# IP_04_00_000-PendulumSchem.net
KiCad netlist of a schematic drawn in EAGLE
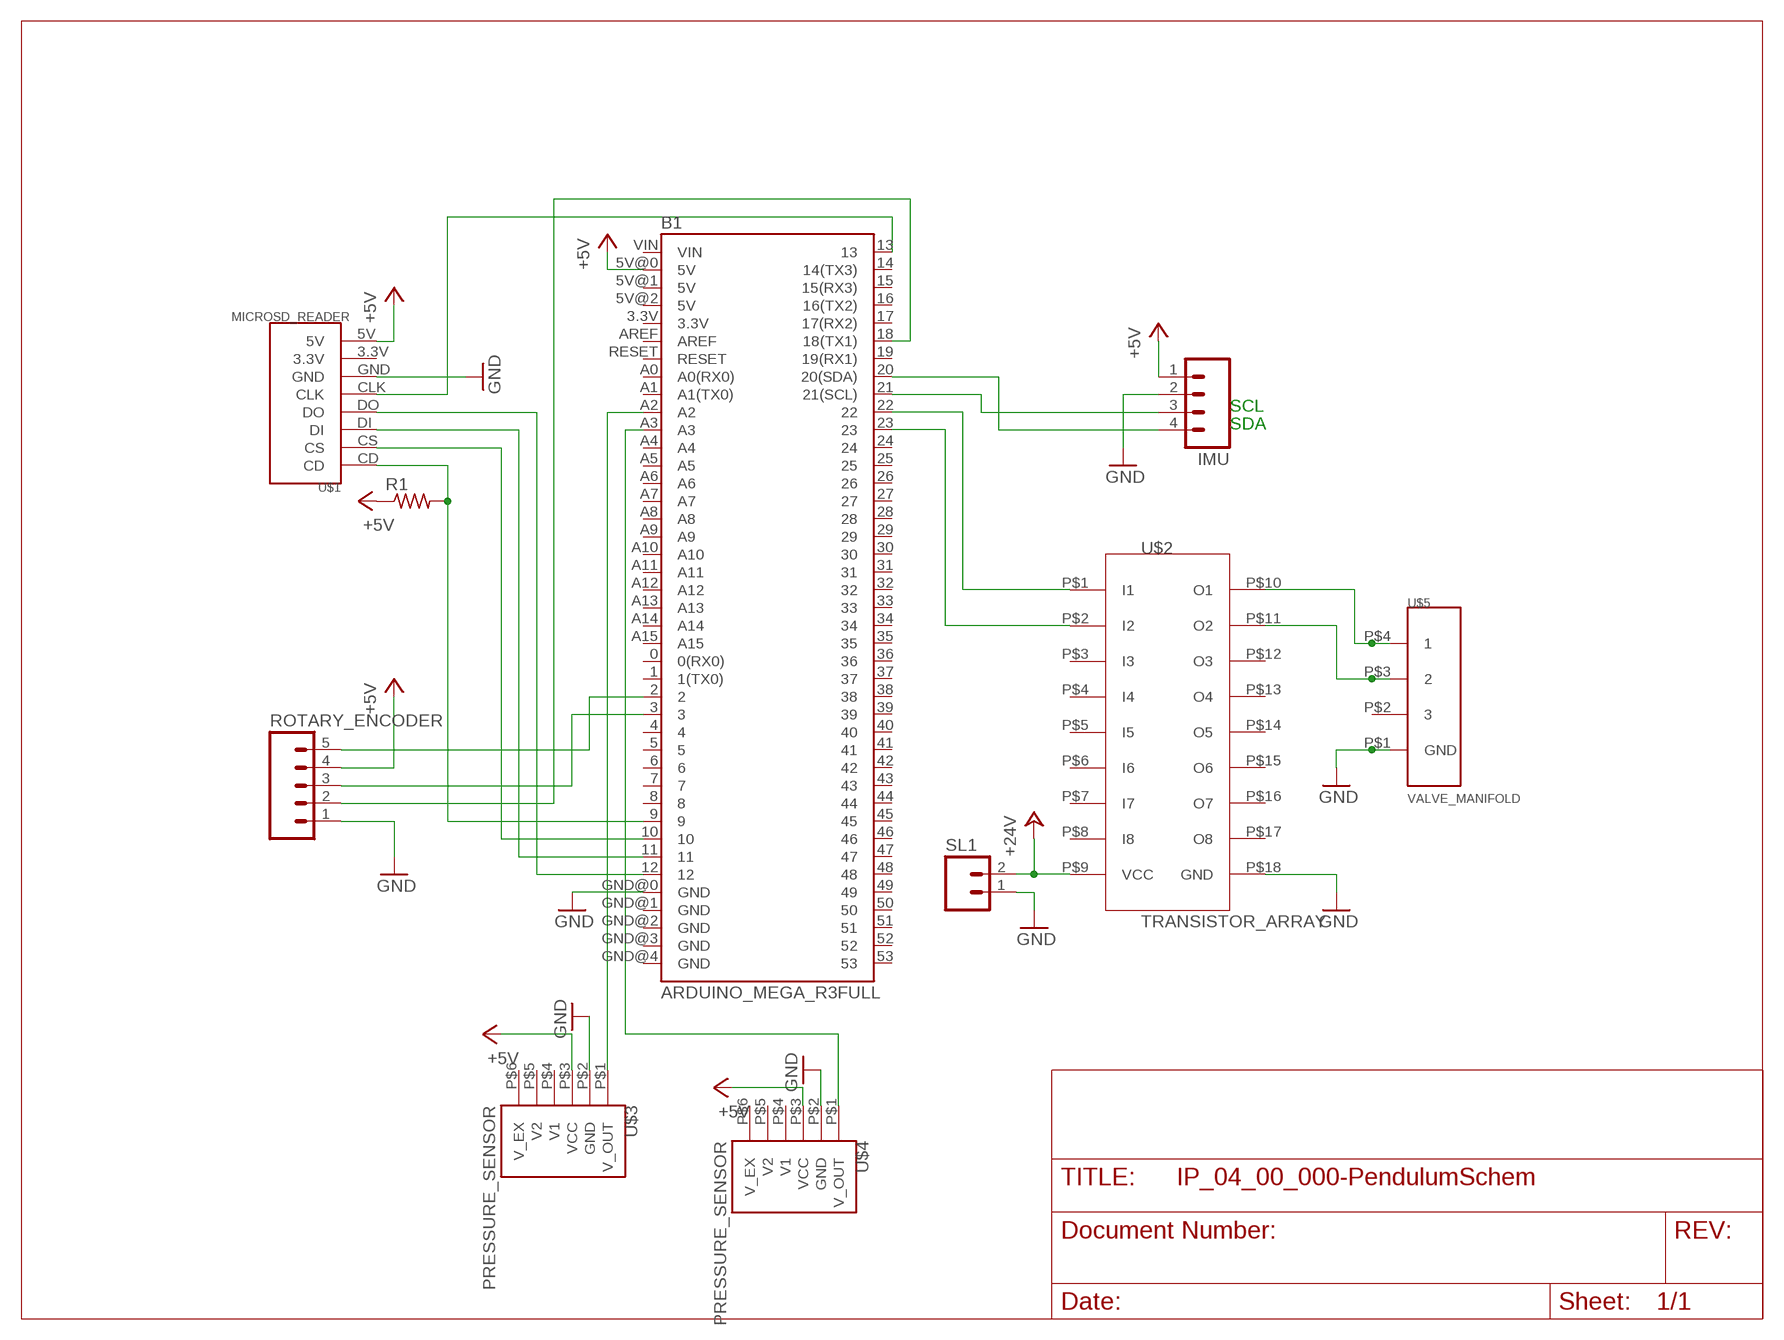
[diagram p0: schematic, sheet 1]

(export (version "E")
  (design (tool "Eeschema 10.0.6"))
  (components
    (comp (ref "B1")
      (value "ARDUINO_MEGA_R3FULL")
      (footprint "eagle-import:ARDUINO_MEGA")
      (libsource (lib "eagle-import") (part "ARDUINO_MEGA_R3FULL"))
    )
    (comp (ref "IMU")
      (value "M04")
      (footprint "eagle-import:04P")
      (libsource (lib "eagle-import") (part "M04"))
    )
    (comp (ref "R1")
      (value "R-US_0204/7")
      (footprint "eagle-import:0204_7")
      (libsource (lib "eagle-import") (part "R-US_0204/7"))
    )
    (comp (ref "ROTARY_ENCODER")
      (value "M05")
      (footprint "eagle-import:05P")
      (libsource (lib "eagle-import") (part "M05"))
    )
    (comp (ref "SL1")
      (value "M02")
      (footprint "eagle-import:02P")
      (libsource (lib "eagle-import") (part "M02"))
    )
    (comp (ref "U$1")
      (value "MICROSD_READER")
      (footprint "eagle-import:MICROSD_READER")
      (libsource (lib "eagle-import") (part "MICROSD_READER"))
    )
    (comp (ref "U$2")
      (value "TRANSISTOR_ARRAY")
      (footprint "eagle-import:TRANSISTOR_ARRAY")
      (libsource (lib "eagle-import") (part "TRANSISTOR_ARRAY"))
    )
    (comp (ref "U$3")
      (value "PRESSURE_SENSOR")
      (footprint "eagle-import:PRESSURE_SENSOR")
      (libsource (lib "eagle-import") (part "PRESSURE_SENSOR"))
    )
    (comp (ref "U$4")
      (value "PRESSURE_SENSOR")
      (footprint "eagle-import:PRESSURE_SENSOR")
      (libsource (lib "eagle-import") (part "PRESSURE_SENSOR"))
    )
    (comp (ref "U$5")
      (value "VALVE_MANIFOLD")
      (footprint "eagle-import:VALVE_MANIFOLD")
      (libsource (lib "eagle-import") (part "VALVE_MANIFOLD"))
    )
  )
  (nets
    (net (code "1") (name "+5V") (class "Default")
      (node (ref "B1") (pin "5V@0") (pinfunction "5V_5V@0") (pintype "bidirectional"))
      (node (ref "IMU") (pin "1") (pinfunction "1_1") (pintype "passive"))
      (node (ref "R1") (pin "1") (pinfunction "1_1") (pintype "passive"))
      (node (ref "ROTARY_ENCODER") (pin "4") (pinfunction "4_4") (pintype "passive"))
      (node (ref "U$1") (pin "5V") (pinfunction "5V_5V") (pintype "bidirectional"))
      (node (ref "U$3") (pin "P$3") (pinfunction "VCC_P$3") (pintype "bidirectional"))
      (node (ref "U$4") (pin "P$3") (pinfunction "VCC_P$3") (pintype "bidirectional"))
    )
    (net (code "2") (name "+24V") (class "Default")
      (node (ref "SL1") (pin "2") (pinfunction "2_2") (pintype "passive"))
      (node (ref "U$2") (pin "P$9") (pinfunction "VCC_P$9") (pintype "bidirectional"))
    )
    (net (code "3") (name "GND") (class "Default")
      (node (ref "B1") (pin "GND@0") (pinfunction "GND_GND@0") (pintype "bidirectional"))
      (node (ref "IMU") (pin "2") (pinfunction "2_2") (pintype "passive"))
      (node (ref "ROTARY_ENCODER") (pin "1") (pinfunction "1_1") (pintype "passive"))
      (node (ref "SL1") (pin "1") (pinfunction "1_1") (pintype "passive"))
      (node (ref "U$1") (pin "GND") (pinfunction "GND_GND") (pintype "bidirectional"))
      (node (ref "U$2") (pin "P$18") (pinfunction "GND_P$18") (pintype "bidirectional"))
      (node (ref "U$3") (pin "P$2") (pinfunction "GND_P$2") (pintype "bidirectional"))
      (node (ref "U$4") (pin "P$2") (pinfunction "GND_P$2") (pintype "bidirectional"))
      (node (ref "U$5") (pin "P$1") (pinfunction "GND_P$1") (pintype "bidirectional"))
    )
    (net (code "4") (name "Net-(B1-18(TX1))") (class "Default")
      (node (ref "B1") (pin "18") (pinfunction "18(TX1)_18") (pintype "bidirectional"))
      (node (ref "ROTARY_ENCODER") (pin "2") (pinfunction "2_2") (pintype "passive"))
    )
    (net (code "5") (name "Net-(B1-20(SDA))") (class "Default")
      (node (ref "B1") (pin "20") (pinfunction "20(SDA)_20") (pintype "bidirectional"))
      (node (ref "IMU") (pin "4") (pinfunction "4_4") (pintype "passive"))
    )
    (net (code "6") (name "Net-(B1-21(SCL))") (class "Default")
      (node (ref "B1") (pin "21") (pinfunction "21(SCL)_21") (pintype "bidirectional"))
      (node (ref "IMU") (pin "3") (pinfunction "3_3") (pintype "passive"))
    )
    (net (code "7") (name "Net-(B1-Pad2)") (class "Default")
      (node (ref "B1") (pin "2") (pinfunction "2_2") (pintype "bidirectional"))
      (node (ref "ROTARY_ENCODER") (pin "5") (pinfunction "5_5") (pintype "passive"))
    )
    (net (code "8") (name "Net-(B1-Pad3)") (class "Default")
      (node (ref "B1") (pin "3") (pinfunction "3_3") (pintype "bidirectional"))
      (node (ref "ROTARY_ENCODER") (pin "3") (pinfunction "3_3") (pintype "passive"))
    )
    (net (code "9") (name "Net-(B1-Pad9)") (class "Default")
      (node (ref "B1") (pin "9") (pinfunction "9_9") (pintype "bidirectional"))
      (node (ref "R1") (pin "2") (pinfunction "2_2") (pintype "passive"))
      (node (ref "U$1") (pin "CD") (pinfunction "CD_CD") (pintype "bidirectional"))
    )
    (net (code "10") (name "Net-(B1-Pad10)") (class "Default")
      (node (ref "B1") (pin "10") (pinfunction "10_10") (pintype "bidirectional"))
      (node (ref "U$1") (pin "CS") (pinfunction "CS_CS") (pintype "bidirectional"))
    )
    (net (code "11") (name "Net-(B1-Pad11)") (class "Default")
      (node (ref "B1") (pin "11") (pinfunction "11_11") (pintype "bidirectional"))
      (node (ref "U$1") (pin "DI") (pinfunction "DI_DI") (pintype "bidirectional"))
    )
    (net (code "12") (name "Net-(B1-Pad12)") (class "Default")
      (node (ref "B1") (pin "12") (pinfunction "12_12") (pintype "bidirectional"))
      (node (ref "U$1") (pin "DO") (pinfunction "DO_DO") (pintype "bidirectional"))
    )
    (net (code "13") (name "Net-(B1-Pad13)") (class "Default")
      (node (ref "B1") (pin "13") (pinfunction "13_13") (pintype "bidirectional"))
      (node (ref "U$1") (pin "CLK") (pinfunction "CLK_CLK") (pintype "bidirectional"))
    )
    (net (code "14") (name "Net-(U$2-I1)") (class "Default")
      (node (ref "B1") (pin "22") (pinfunction "22_22") (pintype "bidirectional"))
      (node (ref "U$2") (pin "P$1") (pinfunction "I1_P$1") (pintype "bidirectional"))
    )
    (net (code "15") (name "Net-(U$2-I2)") (class "Default")
      (node (ref "B1") (pin "23") (pinfunction "23_23") (pintype "bidirectional"))
      (node (ref "U$2") (pin "P$2") (pinfunction "I2_P$2") (pintype "bidirectional"))
    )
    (net (code "16") (name "Net-(U$2-O1)") (class "Default")
      (node (ref "U$2") (pin "P$10") (pinfunction "O1_P$10") (pintype "bidirectional"))
      (node (ref "U$5") (pin "P$4") (pinfunction "1_P$4") (pintype "bidirectional"))
    )
    (net (code "17") (name "Net-(U$2-O2)") (class "Default")
      (node (ref "U$2") (pin "P$11") (pinfunction "O2_P$11") (pintype "bidirectional"))
      (node (ref "U$5") (pin "P$3") (pinfunction "2_P$3") (pintype "bidirectional"))
    )
    (net (code "18") (name "Net-(U$3-V_OUT)") (class "Default")
      (node (ref "B1") (pin "A2") (pinfunction "A2_A2") (pintype "bidirectional"))
      (node (ref "U$3") (pin "P$1") (pinfunction "V_OUT_P$1") (pintype "bidirectional"))
    )
    (net (code "19") (name "Net-(U$4-V_OUT)") (class "Default")
      (node (ref "B1") (pin "A3") (pinfunction "A3_A3") (pintype "bidirectional"))
      (node (ref "U$4") (pin "P$1") (pinfunction "V_OUT_P$1") (pintype "bidirectional"))
    )
    (net (code "20") (name "unconnected-(B1-0(RX0)-Pad0)") (class "Default")
      (node (ref "B1") (pin "0") (pinfunction "0(RX0)_0") (pintype "bidirectional"))
    )
    (net (code "21") (name "unconnected-(B1-1(TX0)-Pad1)") (class "Default")
      (node (ref "B1") (pin "1") (pinfunction "1(TX0)_1") (pintype "bidirectional"))
    )
    (net (code "22") (name "unconnected-(B1-5V-Pad5V@1)") (class "Default")
      (node (ref "B1") (pin "5V@1") (pinfunction "5V_5V@1") (pintype "bidirectional"))
    )
    (net (code "23") (name "unconnected-(B1-5V-Pad5V@2)") (class "Default")
      (node (ref "B1") (pin "5V@2") (pinfunction "5V_5V@2") (pintype "bidirectional"))
    )
    (net (code "24") (name "unconnected-(B1-14(TX3)-Pad14)") (class "Default")
      (node (ref "B1") (pin "14") (pinfunction "14(TX3)_14") (pintype "bidirectional"))
    )
    (net (code "25") (name "unconnected-(B1-15(RX3)-Pad15)") (class "Default")
      (node (ref "B1") (pin "15") (pinfunction "15(RX3)_15") (pintype "bidirectional"))
    )
    (net (code "26") (name "unconnected-(B1-16(TX2)-Pad16)") (class "Default")
      (node (ref "B1") (pin "16") (pinfunction "16(TX2)_16") (pintype "bidirectional"))
    )
    (net (code "27") (name "unconnected-(B1-17(RX2)-Pad17)") (class "Default")
      (node (ref "B1") (pin "17") (pinfunction "17(RX2)_17") (pintype "bidirectional"))
    )
    (net (code "28") (name "unconnected-(B1-19(RX1)-Pad19)") (class "Default")
      (node (ref "B1") (pin "19") (pinfunction "19(RX1)_19") (pintype "bidirectional"))
    )
    (net (code "29") (name "unconnected-(B1-A0(RX0)-PadA0)") (class "Default")
      (node (ref "B1") (pin "A0") (pinfunction "A0(RX0)_A0") (pintype "bidirectional"))
    )
    (net (code "30") (name "unconnected-(B1-A1(TX0)-PadA1)") (class "Default")
      (node (ref "B1") (pin "A1") (pinfunction "A1(TX0)_A1") (pintype "bidirectional"))
    )
    (net (code "31") (name "unconnected-(B1-GND-PadGND@1)") (class "Default")
      (node (ref "B1") (pin "GND@1") (pinfunction "GND_GND@1") (pintype "bidirectional"))
    )
    (net (code "32") (name "unconnected-(B1-GND-PadGND@2)") (class "Default")
      (node (ref "B1") (pin "GND@2") (pinfunction "GND_GND@2") (pintype "bidirectional"))
    )
    (net (code "33") (name "unconnected-(B1-GND-PadGND@3)") (class "Default")
      (node (ref "B1") (pin "GND@3") (pinfunction "GND_GND@3") (pintype "bidirectional"))
    )
    (net (code "34") (name "unconnected-(B1-GND-PadGND@4)") (class "Default")
      (node (ref "B1") (pin "GND@4") (pinfunction "GND_GND@4") (pintype "bidirectional"))
    )
    (net (code "35") (name "unconnected-(B1-Pad3.3V)") (class "Default")
      (node (ref "B1") (pin "3.3V") (pinfunction "3.3V_3.3V") (pintype "bidirectional"))
    )
    (net (code "36") (name "unconnected-(B1-Pad4)") (class "Default")
      (node (ref "B1") (pin "4") (pinfunction "4_4") (pintype "bidirectional"))
    )
    (net (code "37") (name "unconnected-(B1-Pad5)") (class "Default")
      (node (ref "B1") (pin "5") (pinfunction "5_5") (pintype "bidirectional"))
    )
    (net (code "38") (name "unconnected-(B1-Pad6)") (class "Default")
      (node (ref "B1") (pin "6") (pinfunction "6_6") (pintype "bidirectional"))
    )
    (net (code "39") (name "unconnected-(B1-Pad7)") (class "Default")
      (node (ref "B1") (pin "7") (pinfunction "7_7") (pintype "bidirectional"))
    )
    (net (code "40") (name "unconnected-(B1-Pad8)") (class "Default")
      (node (ref "B1") (pin "8") (pinfunction "8_8") (pintype "bidirectional"))
    )
    (net (code "41") (name "unconnected-(B1-Pad24)") (class "Default")
      (node (ref "B1") (pin "24") (pinfunction "24_24") (pintype "bidirectional"))
    )
    (net (code "42") (name "unconnected-(B1-Pad25)") (class "Default")
      (node (ref "B1") (pin "25") (pinfunction "25_25") (pintype "bidirectional"))
    )
    (net (code "43") (name "unconnected-(B1-Pad26)") (class "Default")
      (node (ref "B1") (pin "26") (pinfunction "26_26") (pintype "bidirectional"))
    )
    (net (code "44") (name "unconnected-(B1-Pad27)") (class "Default")
      (node (ref "B1") (pin "27") (pinfunction "27_27") (pintype "bidirectional"))
    )
    (net (code "45") (name "unconnected-(B1-Pad28)") (class "Default")
      (node (ref "B1") (pin "28") (pinfunction "28_28") (pintype "bidirectional"))
    )
    (net (code "46") (name "unconnected-(B1-Pad29)") (class "Default")
      (node (ref "B1") (pin "29") (pinfunction "29_29") (pintype "bidirectional"))
    )
    (net (code "47") (name "unconnected-(B1-Pad30)") (class "Default")
      (node (ref "B1") (pin "30") (pinfunction "30_30") (pintype "bidirectional"))
    )
    (net (code "48") (name "unconnected-(B1-Pad31)") (class "Default")
      (node (ref "B1") (pin "31") (pinfunction "31_31") (pintype "bidirectional"))
    )
    (net (code "49") (name "unconnected-(B1-Pad32)") (class "Default")
      (node (ref "B1") (pin "32") (pinfunction "32_32") (pintype "bidirectional"))
    )
    (net (code "50") (name "unconnected-(B1-Pad33)") (class "Default")
      (node (ref "B1") (pin "33") (pinfunction "33_33") (pintype "bidirectional"))
    )
    (net (code "51") (name "unconnected-(B1-Pad34)") (class "Default")
      (node (ref "B1") (pin "34") (pinfunction "34_34") (pintype "bidirectional"))
    )
    (net (code "52") (name "unconnected-(B1-Pad35)") (class "Default")
      (node (ref "B1") (pin "35") (pinfunction "35_35") (pintype "bidirectional"))
    )
    (net (code "53") (name "unconnected-(B1-Pad36)") (class "Default")
      (node (ref "B1") (pin "36") (pinfunction "36_36") (pintype "bidirectional"))
    )
    (net (code "54") (name "unconnected-(B1-Pad37)") (class "Default")
      (node (ref "B1") (pin "37") (pinfunction "37_37") (pintype "bidirectional"))
    )
    (net (code "55") (name "unconnected-(B1-Pad38)") (class "Default")
      (node (ref "B1") (pin "38") (pinfunction "38_38") (pintype "bidirectional"))
    )
    (net (code "56") (name "unconnected-(B1-Pad39)") (class "Default")
      (node (ref "B1") (pin "39") (pinfunction "39_39") (pintype "bidirectional"))
    )
    (net (code "57") (name "unconnected-(B1-Pad40)") (class "Default")
      (node (ref "B1") (pin "40") (pinfunction "40_40") (pintype "bidirectional"))
    )
    (net (code "58") (name "unconnected-(B1-Pad41)") (class "Default")
      (node (ref "B1") (pin "41") (pinfunction "41_41") (pintype "bidirectional"))
    )
    (net (code "59") (name "unconnected-(B1-Pad42)") (class "Default")
      (node (ref "B1") (pin "42") (pinfunction "42_42") (pintype "bidirectional"))
    )
    (net (code "60") (name "unconnected-(B1-Pad43)") (class "Default")
      (node (ref "B1") (pin "43") (pinfunction "43_43") (pintype "bidirectional"))
    )
    (net (code "61") (name "unconnected-(B1-Pad44)") (class "Default")
      (node (ref "B1") (pin "44") (pinfunction "44_44") (pintype "bidirectional"))
    )
    (net (code "62") (name "unconnected-(B1-Pad45)") (class "Default")
      (node (ref "B1") (pin "45") (pinfunction "45_45") (pintype "bidirectional"))
    )
    (net (code "63") (name "unconnected-(B1-Pad46)") (class "Default")
      (node (ref "B1") (pin "46") (pinfunction "46_46") (pintype "bidirectional"))
    )
    (net (code "64") (name "unconnected-(B1-Pad47)") (class "Default")
      (node (ref "B1") (pin "47") (pinfunction "47_47") (pintype "bidirectional"))
    )
    (net (code "65") (name "unconnected-(B1-Pad48)") (class "Default")
      (node (ref "B1") (pin "48") (pinfunction "48_48") (pintype "bidirectional"))
    )
    (net (code "66") (name "unconnected-(B1-Pad49)") (class "Default")
      (node (ref "B1") (pin "49") (pinfunction "49_49") (pintype "bidirectional"))
    )
    (net (code "67") (name "unconnected-(B1-Pad50)") (class "Default")
      (node (ref "B1") (pin "50") (pinfunction "50_50") (pintype "bidirectional"))
    )
    (net (code "68") (name "unconnected-(B1-Pad51)") (class "Default")
      (node (ref "B1") (pin "51") (pinfunction "51_51") (pintype "bidirectional"))
    )
    (net (code "69") (name "unconnected-(B1-Pad52)") (class "Default")
      (node (ref "B1") (pin "52") (pinfunction "52_52") (pintype "bidirectional"))
    )
    (net (code "70") (name "unconnected-(B1-Pad53)") (class "Default")
      (node (ref "B1") (pin "53") (pinfunction "53_53") (pintype "bidirectional"))
    )
    (net (code "71") (name "unconnected-(B1-PadA4)") (class "Default")
      (node (ref "B1") (pin "A4") (pinfunction "A4_A4") (pintype "bidirectional"))
    )
    (net (code "72") (name "unconnected-(B1-PadA5)") (class "Default")
      (node (ref "B1") (pin "A5") (pinfunction "A5_A5") (pintype "bidirectional"))
    )
    (net (code "73") (name "unconnected-(B1-PadA6)") (class "Default")
      (node (ref "B1") (pin "A6") (pinfunction "A6_A6") (pintype "bidirectional"))
    )
    (net (code "74") (name "unconnected-(B1-PadA7)") (class "Default")
      (node (ref "B1") (pin "A7") (pinfunction "A7_A7") (pintype "bidirectional"))
    )
    (net (code "75") (name "unconnected-(B1-PadA8)") (class "Default")
      (node (ref "B1") (pin "A8") (pinfunction "A8_A8") (pintype "bidirectional"))
    )
    (net (code "76") (name "unconnected-(B1-PadA9)") (class "Default")
      (node (ref "B1") (pin "A9") (pinfunction "A9_A9") (pintype "bidirectional"))
    )
    (net (code "77") (name "unconnected-(B1-PadA10)") (class "Default")
      (node (ref "B1") (pin "A10") (pinfunction "A10_A10") (pintype "bidirectional"))
    )
    (net (code "78") (name "unconnected-(B1-PadA11)") (class "Default")
      (node (ref "B1") (pin "A11") (pinfunction "A11_A11") (pintype "bidirectional"))
    )
    (net (code "79") (name "unconnected-(B1-PadA12)") (class "Default")
      (node (ref "B1") (pin "A12") (pinfunction "A12_A12") (pintype "bidirectional"))
    )
    (net (code "80") (name "unconnected-(B1-PadA13)") (class "Default")
      (node (ref "B1") (pin "A13") (pinfunction "A13_A13") (pintype "bidirectional"))
    )
    (net (code "81") (name "unconnected-(B1-PadA14)") (class "Default")
      (node (ref "B1") (pin "A14") (pinfunction "A14_A14") (pintype "bidirectional"))
    )
    (net (code "82") (name "unconnected-(B1-PadA15)") (class "Default")
      (node (ref "B1") (pin "A15") (pinfunction "A15_A15") (pintype "bidirectional"))
    )
    (net (code "83") (name "unconnected-(B1-PadAREF)") (class "Default")
      (node (ref "B1") (pin "AREF") (pinfunction "AREF_AREF") (pintype "bidirectional"))
    )
    (net (code "84") (name "unconnected-(B1-PadRESET)") (class "Default")
      (node (ref "B1") (pin "RESET") (pinfunction "RESET_RESET") (pintype "bidirectional"))
    )
    (net (code "85") (name "unconnected-(B1-PadVIN)") (class "Default")
      (node (ref "B1") (pin "VIN") (pinfunction "VIN_VIN") (pintype "bidirectional"))
    )
    (net (code "86") (name "unconnected-(U$1-Pad3.3V)") (class "Default")
      (node (ref "U$1") (pin "3.3V") (pinfunction "3.3V_3.3V") (pintype "bidirectional"))
    )
    (net (code "87") (name "unconnected-(U$2-I3-PadP$3)") (class "Default")
      (node (ref "U$2") (pin "P$3") (pinfunction "I3_P$3") (pintype "bidirectional"))
    )
    (net (code "88") (name "unconnected-(U$2-I4-PadP$4)") (class "Default")
      (node (ref "U$2") (pin "P$4") (pinfunction "I4_P$4") (pintype "bidirectional"))
    )
    (net (code "89") (name "unconnected-(U$2-I5-PadP$5)") (class "Default")
      (node (ref "U$2") (pin "P$5") (pinfunction "I5_P$5") (pintype "bidirectional"))
    )
    (net (code "90") (name "unconnected-(U$2-I6-PadP$6)") (class "Default")
      (node (ref "U$2") (pin "P$6") (pinfunction "I6_P$6") (pintype "bidirectional"))
    )
    (net (code "91") (name "unconnected-(U$2-I7-PadP$7)") (class "Default")
      (node (ref "U$2") (pin "P$7") (pinfunction "I7_P$7") (pintype "bidirectional"))
    )
    (net (code "92") (name "unconnected-(U$2-I8-PadP$8)") (class "Default")
      (node (ref "U$2") (pin "P$8") (pinfunction "I8_P$8") (pintype "bidirectional"))
    )
    (net (code "93") (name "unconnected-(U$2-O3-PadP$12)") (class "Default")
      (node (ref "U$2") (pin "P$12") (pinfunction "O3_P$12") (pintype "bidirectional"))
    )
    (net (code "94") (name "unconnected-(U$2-O4-PadP$13)") (class "Default")
      (node (ref "U$2") (pin "P$13") (pinfunction "O4_P$13") (pintype "bidirectional"))
    )
    (net (code "95") (name "unconnected-(U$2-O5-PadP$14)") (class "Default")
      (node (ref "U$2") (pin "P$14") (pinfunction "O5_P$14") (pintype "bidirectional"))
    )
    (net (code "96") (name "unconnected-(U$2-O6-PadP$15)") (class "Default")
      (node (ref "U$2") (pin "P$15") (pinfunction "O6_P$15") (pintype "bidirectional"))
    )
    (net (code "97") (name "unconnected-(U$2-O7-PadP$16)") (class "Default")
      (node (ref "U$2") (pin "P$16") (pinfunction "O7_P$16") (pintype "bidirectional"))
    )
    (net (code "98") (name "unconnected-(U$2-O8-PadP$17)") (class "Default")
      (node (ref "U$2") (pin "P$17") (pinfunction "O8_P$17") (pintype "bidirectional"))
    )
    (net (code "99") (name "unconnected-(U$3-V1-PadP$4)") (class "Default")
      (node (ref "U$3") (pin "P$4") (pinfunction "V1_P$4") (pintype "bidirectional"))
    )
    (net (code "100") (name "unconnected-(U$3-V2-PadP$5)") (class "Default")
      (node (ref "U$3") (pin "P$5") (pinfunction "V2_P$5") (pintype "bidirectional"))
    )
    (net (code "101") (name "unconnected-(U$3-V_EX-PadP$6)") (class "Default")
      (node (ref "U$3") (pin "P$6") (pinfunction "V_EX_P$6") (pintype "bidirectional"))
    )
    (net (code "102") (name "unconnected-(U$4-V1-PadP$4)") (class "Default")
      (node (ref "U$4") (pin "P$4") (pinfunction "V1_P$4") (pintype "bidirectional"))
    )
    (net (code "103") (name "unconnected-(U$4-V2-PadP$5)") (class "Default")
      (node (ref "U$4") (pin "P$5") (pinfunction "V2_P$5") (pintype "bidirectional"))
    )
    (net (code "104") (name "unconnected-(U$4-V_EX-PadP$6)") (class "Default")
      (node (ref "U$4") (pin "P$6") (pinfunction "V_EX_P$6") (pintype "bidirectional"))
    )
    (net (code "105") (name "unconnected-(U$5-3-PadP$2)") (class "Default")
      (node (ref "U$5") (pin "P$2") (pinfunction "3_P$2") (pintype "bidirectional"))
    )
  )
)
